# PWR_HT4928S.net
KiCad netlist of a schematic drawn in Altium Designer
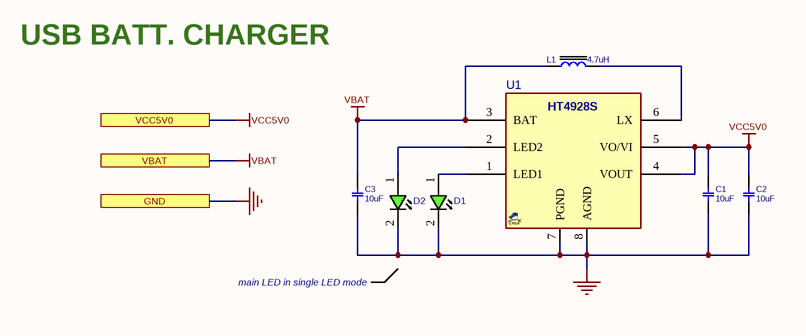
[diagram p0: PWR_HT4928S.SchDoc]

(export (version "E")
  (design (tool "Eeschema 10.0.6"))
  (components
    (comp (ref "C1")
      (value "10uF")
      (footprint "C0402")
      (description "CAP, MLCC")
      (fields (field (name "MANF_P#") "CL05A106MP5NUNC") (field (name "MANF") "Samsung"))
      (libsource (lib "passive_smd") (part "CAP_SMD_MLCC"))
    )
    (comp (ref "C2")
      (value "10uF")
      (footprint "C0402")
      (description "CAP, MLCC")
      (fields (field (name "MANF_P#") "CL05A106MP5NUNC") (field (name "MANF") "Samsung"))
      (libsource (lib "passive_smd") (part "CAP_SMD_MLCC"))
    )
    (comp (ref "C3")
      (value "10uF")
      (footprint "C0402")
      (description "CAP, MLCC")
      (fields (field (name "MANF_P#") "CL05A106MP5NUNC") (field (name "MANF") "Samsung"))
      (libsource (lib "passive_smd") (part "CAP_SMD_MLCC"))
    )
    (comp (ref "D1")
      (value "LED603GRN")
      (footprint "LED0603GRN")
      (description "LED, SMD, 0603, GREEN")
      (fields (field (name "MANF") "Kingbright") (field (name "MANF_P#") "APT1608SGC"))
      (libsource (lib "led(diode)") (part "LED_SMD_0603_GRN"))
    )
    (comp (ref "D2")
      (value "LED603GRN")
      (footprint "LED0603GRN")
      (description "LED, SMD, 0603, GREEN")
      (fields (field (name "MANF") "Kingbright") (field (name "MANF_P#") "APT1608SGC"))
      (libsource (lib "led(diode)") (part "LED_SMD_0603_GRN"))
    )
    (comp (ref "L1")
      (value "4.7uH")
      (footprint "L_3")
      (description "INDUCTOR")
      (fields (field (name "MANF_P#") "NRH3012T4R7MN") (field (name "MANF") "Murata"))
      (libsource (lib "inductor_power") (part "IND_SMD_2.2uH_2.6A"))
    )
    (comp (ref "U1")
      (value "HT4928S")
      (footprint "SO_8")
      (description "IC, CHARGER and Boost for USB mobile")
      (fields (field (name "MANF") "HOTCHIP"))
      (libsource (lib "pwr_reg_pmic") (part "HT4928S_SOP8"))
    )
  )
  (nets
    (net (code "1") (name "GND") (class "Default")
      (node (ref "C1") (pin "1") (pinfunction "1_1") (pintype "passive"))
      (node (ref "C2") (pin "1") (pinfunction "1_1") (pintype "passive"))
      (node (ref "C3") (pin "1") (pinfunction "1_1") (pintype "passive"))
      (node (ref "D1") (pin "2") (pinfunction "CATHODE_2") (pintype "passive"))
      (node (ref "D2") (pin "2") (pinfunction "CATHODE_2") (pintype "passive"))
      (node (ref "U1") (pin "7") (pinfunction "PGND_7") (pintype "passive"))
      (node (ref "U1") (pin "8") (pinfunction "AGND_8") (pintype "passive"))
    )
    (net (code "2") (name "Net-(D1-ANODE)") (class "Default")
      (node (ref "D1") (pin "1") (pinfunction "ANODE_1") (pintype "passive"))
      (node (ref "U1") (pin "1") (pinfunction "LED1_1") (pintype "passive"))
    )
    (net (code "3") (name "Net-(D2-ANODE)") (class "Default")
      (node (ref "D2") (pin "1") (pinfunction "ANODE_1") (pintype "passive"))
      (node (ref "U1") (pin "2") (pinfunction "LED2_2") (pintype "passive"))
    )
    (net (code "4") (name "Net-(U1-LX)") (class "Default")
      (node (ref "L1") (pin "2") (pinfunction "2_2") (pintype "passive"))
      (node (ref "U1") (pin "6") (pinfunction "LX_6") (pintype "passive"))
    )
    (net (code "5") (name "VBAT") (class "Default")
      (node (ref "C3") (pin "2") (pinfunction "2_2") (pintype "passive"))
      (node (ref "L1") (pin "1") (pinfunction "1_1") (pintype "passive"))
      (node (ref "U1") (pin "3") (pinfunction "BAT_3") (pintype "passive"))
    )
    (net (code "6") (name "VCC5V0") (class "Default")
      (node (ref "C1") (pin "2") (pinfunction "2_2") (pintype "passive"))
      (node (ref "C2") (pin "2") (pinfunction "2_2") (pintype "passive"))
      (node (ref "U1") (pin "4") (pinfunction "VOUT_4") (pintype "passive"))
      (node (ref "U1") (pin "5") (pinfunction "VO/VI_5") (pintype "passive"))
    )
  )
)
